# led-neopixel-SK6812.net
KiCad netlist of a schematic drawn in EAGLE
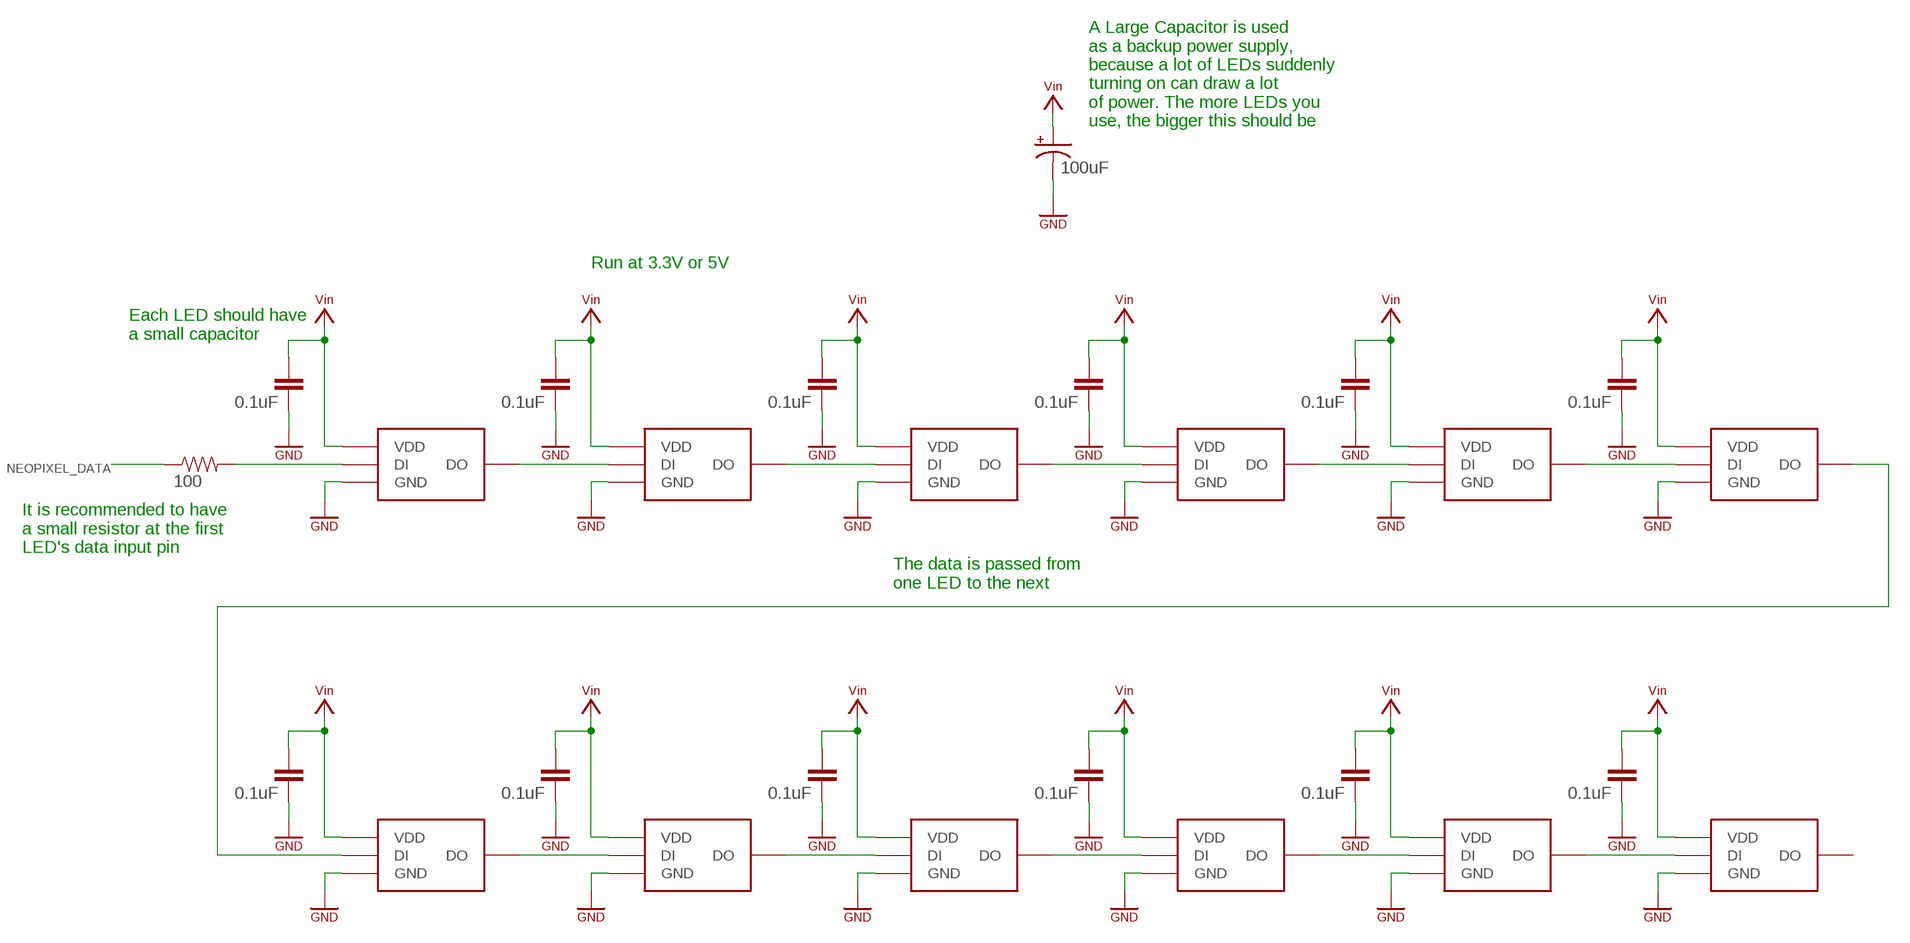
[diagram p0: schematic, sheet 1]

(export (version "E")
  (design (tool "Eeschema 10.0.6"))
  (components
    (comp (ref "C1")
      (value "0.1uF")
      (footprint "eagle-import:0805")
      (libsource (lib "eagle-import") (part "COMPONENT_CAP-0805"))
    )
    (comp (ref "C2")
      (value "0.1uF")
      (footprint "eagle-import:0805")
      (libsource (lib "eagle-import") (part "COMPONENT_CAP-0805"))
    )
    (comp (ref "C3")
      (value "0.1uF")
      (footprint "eagle-import:0805")
      (libsource (lib "eagle-import") (part "COMPONENT_CAP-0805"))
    )
    (comp (ref "C4")
      (value "0.1uF")
      (footprint "eagle-import:0805")
      (libsource (lib "eagle-import") (part "COMPONENT_CAP-0805"))
    )
    (comp (ref "C5")
      (value "0.1uF")
      (footprint "eagle-import:0805")
      (libsource (lib "eagle-import") (part "COMPONENT_CAP-0805"))
    )
    (comp (ref "C6")
      (value "0.1uF")
      (footprint "eagle-import:0805")
      (libsource (lib "eagle-import") (part "COMPONENT_CAP-0805"))
    )
    (comp (ref "C7")
      (value "0.1uF")
      (footprint "eagle-import:0805")
      (libsource (lib "eagle-import") (part "COMPONENT_CAP-0805"))
    )
    (comp (ref "C8")
      (value "0.1uF")
      (footprint "eagle-import:0805")
      (libsource (lib "eagle-import") (part "COMPONENT_CAP-0805"))
    )
    (comp (ref "C9")
      (value "0.1uF")
      (footprint "eagle-import:0805")
      (libsource (lib "eagle-import") (part "COMPONENT_CAP-0805"))
    )
    (comp (ref "C10")
      (value "0.1uF")
      (footprint "eagle-import:0805")
      (libsource (lib "eagle-import") (part "COMPONENT_CAP-0805"))
    )
    (comp (ref "C11")
      (value "0.1uF")
      (footprint "eagle-import:0805")
      (libsource (lib "eagle-import") (part "COMPONENT_CAP-0805"))
    )
    (comp (ref "C12")
      (value "0.1uF")
      (footprint "eagle-import:0805")
      (libsource (lib "eagle-import") (part "COMPONENT_CAP-0805"))
    )
    (comp (ref "C13")
      (value "100uF")
      (footprint "eagle-import:CAP_RADIAL_CAN_8MM")
      (libsource (lib "eagle-import") (part "COMPONENT_CAP_POL-8MM"))
    )
    (comp (ref "LED1")
      (value "LED_NEOPIXEL_SK6812")
      (footprint "eagle-import:SK6812")
      (libsource (lib "eagle-import") (part "LED_NEOPIXEL_SK6812"))
    )
    (comp (ref "LED2")
      (value "LED_NEOPIXEL_SK6812")
      (footprint "eagle-import:SK6812")
      (libsource (lib "eagle-import") (part "LED_NEOPIXEL_SK6812"))
    )
    (comp (ref "LED3")
      (value "LED_NEOPIXEL_SK6812")
      (footprint "eagle-import:SK6812")
      (libsource (lib "eagle-import") (part "LED_NEOPIXEL_SK6812"))
    )
    (comp (ref "LED4")
      (value "LED_NEOPIXEL_SK6812")
      (footprint "eagle-import:SK6812")
      (libsource (lib "eagle-import") (part "LED_NEOPIXEL_SK6812"))
    )
    (comp (ref "LED5")
      (value "LED_NEOPIXEL_SK6812")
      (footprint "eagle-import:SK6812")
      (libsource (lib "eagle-import") (part "LED_NEOPIXEL_SK6812"))
    )
    (comp (ref "LED6")
      (value "LED_NEOPIXEL_SK6812")
      (footprint "eagle-import:SK6812")
      (libsource (lib "eagle-import") (part "LED_NEOPIXEL_SK6812"))
    )
    (comp (ref "LED7")
      (value "LED_NEOPIXEL_SK6812")
      (footprint "eagle-import:SK6812")
      (libsource (lib "eagle-import") (part "LED_NEOPIXEL_SK6812"))
    )
    (comp (ref "LED8")
      (value "LED_NEOPIXEL_SK6812")
      (footprint "eagle-import:SK6812")
      (libsource (lib "eagle-import") (part "LED_NEOPIXEL_SK6812"))
    )
    (comp (ref "LED9")
      (value "LED_NEOPIXEL_SK6812")
      (footprint "eagle-import:SK6812")
      (libsource (lib "eagle-import") (part "LED_NEOPIXEL_SK6812"))
    )
    (comp (ref "LED10")
      (value "LED_NEOPIXEL_SK6812")
      (footprint "eagle-import:SK6812")
      (libsource (lib "eagle-import") (part "LED_NEOPIXEL_SK6812"))
    )
    (comp (ref "LED11")
      (value "LED_NEOPIXEL_SK6812")
      (footprint "eagle-import:SK6812")
      (libsource (lib "eagle-import") (part "LED_NEOPIXEL_SK6812"))
    )
    (comp (ref "LED12")
      (value "LED_NEOPIXEL_SK6812")
      (footprint "eagle-import:SK6812")
      (libsource (lib "eagle-import") (part "LED_NEOPIXEL_SK6812"))
    )
    (comp (ref "R1")
      (value "100")
      (footprint "eagle-import:0805")
      (libsource (lib "eagle-import") (part "COMPONENT_RESISTOR-0805"))
    )
  )
  (nets
    (net (code "1") (name "NEOPIXEL_DATA") (class "Default")
      (node (ref "R1") (pin "1") (pinfunction "1_1") (pintype "passive"))
    )
    (net (code "2") (name "Net-(LED1-DI)") (class "Default")
      (node (ref "LED1") (pin "4-DIN") (pinfunction "DI_4-DIN") (pintype "input"))
      (node (ref "R1") (pin "2") (pinfunction "2_2") (pintype "passive"))
    )
    (net (code "3") (name "Net-(LED1-DO)") (class "Default")
      (node (ref "LED1") (pin "2-DOUT") (pinfunction "DO_2-DOUT") (pintype "output"))
      (node (ref "LED2") (pin "4-DIN") (pinfunction "DI_4-DIN") (pintype "input"))
    )
    (net (code "4") (name "Net-(LED2-DO)") (class "Default")
      (node (ref "LED2") (pin "2-DOUT") (pinfunction "DO_2-DOUT") (pintype "output"))
      (node (ref "LED3") (pin "4-DIN") (pinfunction "DI_4-DIN") (pintype "input"))
    )
    (net (code "5") (name "Net-(LED3-DO)") (class "Default")
      (node (ref "LED3") (pin "2-DOUT") (pinfunction "DO_2-DOUT") (pintype "output"))
      (node (ref "LED4") (pin "4-DIN") (pinfunction "DI_4-DIN") (pintype "input"))
    )
    (net (code "6") (name "Net-(LED4-DO)") (class "Default")
      (node (ref "LED4") (pin "2-DOUT") (pinfunction "DO_2-DOUT") (pintype "output"))
      (node (ref "LED5") (pin "4-DIN") (pinfunction "DI_4-DIN") (pintype "input"))
    )
    (net (code "7") (name "Net-(LED5-DO)") (class "Default")
      (node (ref "LED5") (pin "2-DOUT") (pinfunction "DO_2-DOUT") (pintype "output"))
      (node (ref "LED6") (pin "4-DIN") (pinfunction "DI_4-DIN") (pintype "input"))
    )
    (net (code "8") (name "Net-(LED6-DO)") (class "Default")
      (node (ref "LED6") (pin "2-DOUT") (pinfunction "DO_2-DOUT") (pintype "output"))
      (node (ref "LED7") (pin "4-DIN") (pinfunction "DI_4-DIN") (pintype "input"))
    )
    (net (code "9") (name "Net-(LED7-DO)") (class "Default")
      (node (ref "LED7") (pin "2-DOUT") (pinfunction "DO_2-DOUT") (pintype "output"))
      (node (ref "LED8") (pin "4-DIN") (pinfunction "DI_4-DIN") (pintype "input"))
    )
    (net (code "10") (name "Net-(LED8-DO)") (class "Default")
      (node (ref "LED8") (pin "2-DOUT") (pinfunction "DO_2-DOUT") (pintype "output"))
      (node (ref "LED9") (pin "4-DIN") (pinfunction "DI_4-DIN") (pintype "input"))
    )
    (net (code "11") (name "Net-(LED10-DI)") (class "Default")
      (node (ref "LED10") (pin "4-DIN") (pinfunction "DI_4-DIN") (pintype "input"))
      (node (ref "LED9") (pin "2-DOUT") (pinfunction "DO_2-DOUT") (pintype "output"))
    )
    (net (code "12") (name "Net-(LED10-DO)") (class "Default")
      (node (ref "LED10") (pin "2-DOUT") (pinfunction "DO_2-DOUT") (pintype "output"))
      (node (ref "LED11") (pin "4-DIN") (pinfunction "DI_4-DIN") (pintype "input"))
    )
    (net (code "13") (name "Net-(LED11-DO)") (class "Default")
      (node (ref "LED11") (pin "2-DOUT") (pinfunction "DO_2-DOUT") (pintype "output"))
      (node (ref "LED12") (pin "4-DIN") (pinfunction "DI_4-DIN") (pintype "input"))
    )
    (net (code "14") (name "SYMBOL_GND") (class "Default")
      (node (ref "C1") (pin "2") (pinfunction "2_2") (pintype "passive"))
      (node (ref "C10") (pin "2") (pinfunction "2_2") (pintype "passive"))
      (node (ref "C11") (pin "2") (pinfunction "2_2") (pintype "passive"))
      (node (ref "C12") (pin "2") (pinfunction "2_2") (pintype "passive"))
      (node (ref "C13") (pin "-") (pinfunction "-_-") (pintype "passive"))
      (node (ref "C2") (pin "2") (pinfunction "2_2") (pintype "passive"))
      (node (ref "C3") (pin "2") (pinfunction "2_2") (pintype "passive"))
      (node (ref "C4") (pin "2") (pinfunction "2_2") (pintype "passive"))
      (node (ref "C5") (pin "2") (pinfunction "2_2") (pintype "passive"))
      (node (ref "C6") (pin "2") (pinfunction "2_2") (pintype "passive"))
      (node (ref "C7") (pin "2") (pinfunction "2_2") (pintype "passive"))
      (node (ref "C8") (pin "2") (pinfunction "2_2") (pintype "passive"))
      (node (ref "C9") (pin "2") (pinfunction "2_2") (pintype "passive"))
      (node (ref "LED1") (pin "3-GND") (pinfunction "GND_3-GND") (pintype "power_in"))
      (node (ref "LED10") (pin "3-GND") (pinfunction "GND_3-GND") (pintype "power_in"))
      (node (ref "LED11") (pin "3-GND") (pinfunction "GND_3-GND") (pintype "power_in"))
      (node (ref "LED12") (pin "3-GND") (pinfunction "GND_3-GND") (pintype "power_in"))
      (node (ref "LED2") (pin "3-GND") (pinfunction "GND_3-GND") (pintype "power_in"))
      (node (ref "LED3") (pin "3-GND") (pinfunction "GND_3-GND") (pintype "power_in"))
      (node (ref "LED4") (pin "3-GND") (pinfunction "GND_3-GND") (pintype "power_in"))
      (node (ref "LED5") (pin "3-GND") (pinfunction "GND_3-GND") (pintype "power_in"))
      (node (ref "LED6") (pin "3-GND") (pinfunction "GND_3-GND") (pintype "power_in"))
      (node (ref "LED7") (pin "3-GND") (pinfunction "GND_3-GND") (pintype "power_in"))
      (node (ref "LED8") (pin "3-GND") (pinfunction "GND_3-GND") (pintype "power_in"))
      (node (ref "LED9") (pin "3-GND") (pinfunction "GND_3-GND") (pintype "power_in"))
    )
    (net (code "15") (name "SYMBOL_VIN") (class "Default")
      (node (ref "C1") (pin "1") (pinfunction "1_1") (pintype "passive"))
      (node (ref "C10") (pin "1") (pinfunction "1_1") (pintype "passive"))
      (node (ref "C11") (pin "1") (pinfunction "1_1") (pintype "passive"))
      (node (ref "C12") (pin "1") (pinfunction "1_1") (pintype "passive"))
      (node (ref "C13") (pin "+") (pinfunction "+_+") (pintype "passive"))
      (node (ref "C2") (pin "1") (pinfunction "1_1") (pintype "passive"))
      (node (ref "C3") (pin "1") (pinfunction "1_1") (pintype "passive"))
      (node (ref "C4") (pin "1") (pinfunction "1_1") (pintype "passive"))
      (node (ref "C5") (pin "1") (pinfunction "1_1") (pintype "passive"))
      (node (ref "C6") (pin "1") (pinfunction "1_1") (pintype "passive"))
      (node (ref "C7") (pin "1") (pinfunction "1_1") (pintype "passive"))
      (node (ref "C8") (pin "1") (pinfunction "1_1") (pintype "passive"))
      (node (ref "C9") (pin "1") (pinfunction "1_1") (pintype "passive"))
      (node (ref "LED1") (pin "1-VDD") (pinfunction "VDD_1-VDD") (pintype "power_in"))
      (node (ref "LED10") (pin "1-VDD") (pinfunction "VDD_1-VDD") (pintype "power_in"))
      (node (ref "LED11") (pin "1-VDD") (pinfunction "VDD_1-VDD") (pintype "power_in"))
      (node (ref "LED12") (pin "1-VDD") (pinfunction "VDD_1-VDD") (pintype "power_in"))
      (node (ref "LED2") (pin "1-VDD") (pinfunction "VDD_1-VDD") (pintype "power_in"))
      (node (ref "LED3") (pin "1-VDD") (pinfunction "VDD_1-VDD") (pintype "power_in"))
      (node (ref "LED4") (pin "1-VDD") (pinfunction "VDD_1-VDD") (pintype "power_in"))
      (node (ref "LED5") (pin "1-VDD") (pinfunction "VDD_1-VDD") (pintype "power_in"))
      (node (ref "LED6") (pin "1-VDD") (pinfunction "VDD_1-VDD") (pintype "power_in"))
      (node (ref "LED7") (pin "1-VDD") (pinfunction "VDD_1-VDD") (pintype "power_in"))
      (node (ref "LED8") (pin "1-VDD") (pinfunction "VDD_1-VDD") (pintype "power_in"))
      (node (ref "LED9") (pin "1-VDD") (pinfunction "VDD_1-VDD") (pintype "power_in"))
    )
    (net (code "16") (name "unconnected-(LED12-DO-Pad2-DOUT)") (class "Default")
      (node (ref "LED12") (pin "2-DOUT") (pinfunction "DO_2-DOUT") (pintype "output"))
    )
  )
)
